# Controller.net
KiCad netlist of a schematic drawn in Altium Designer
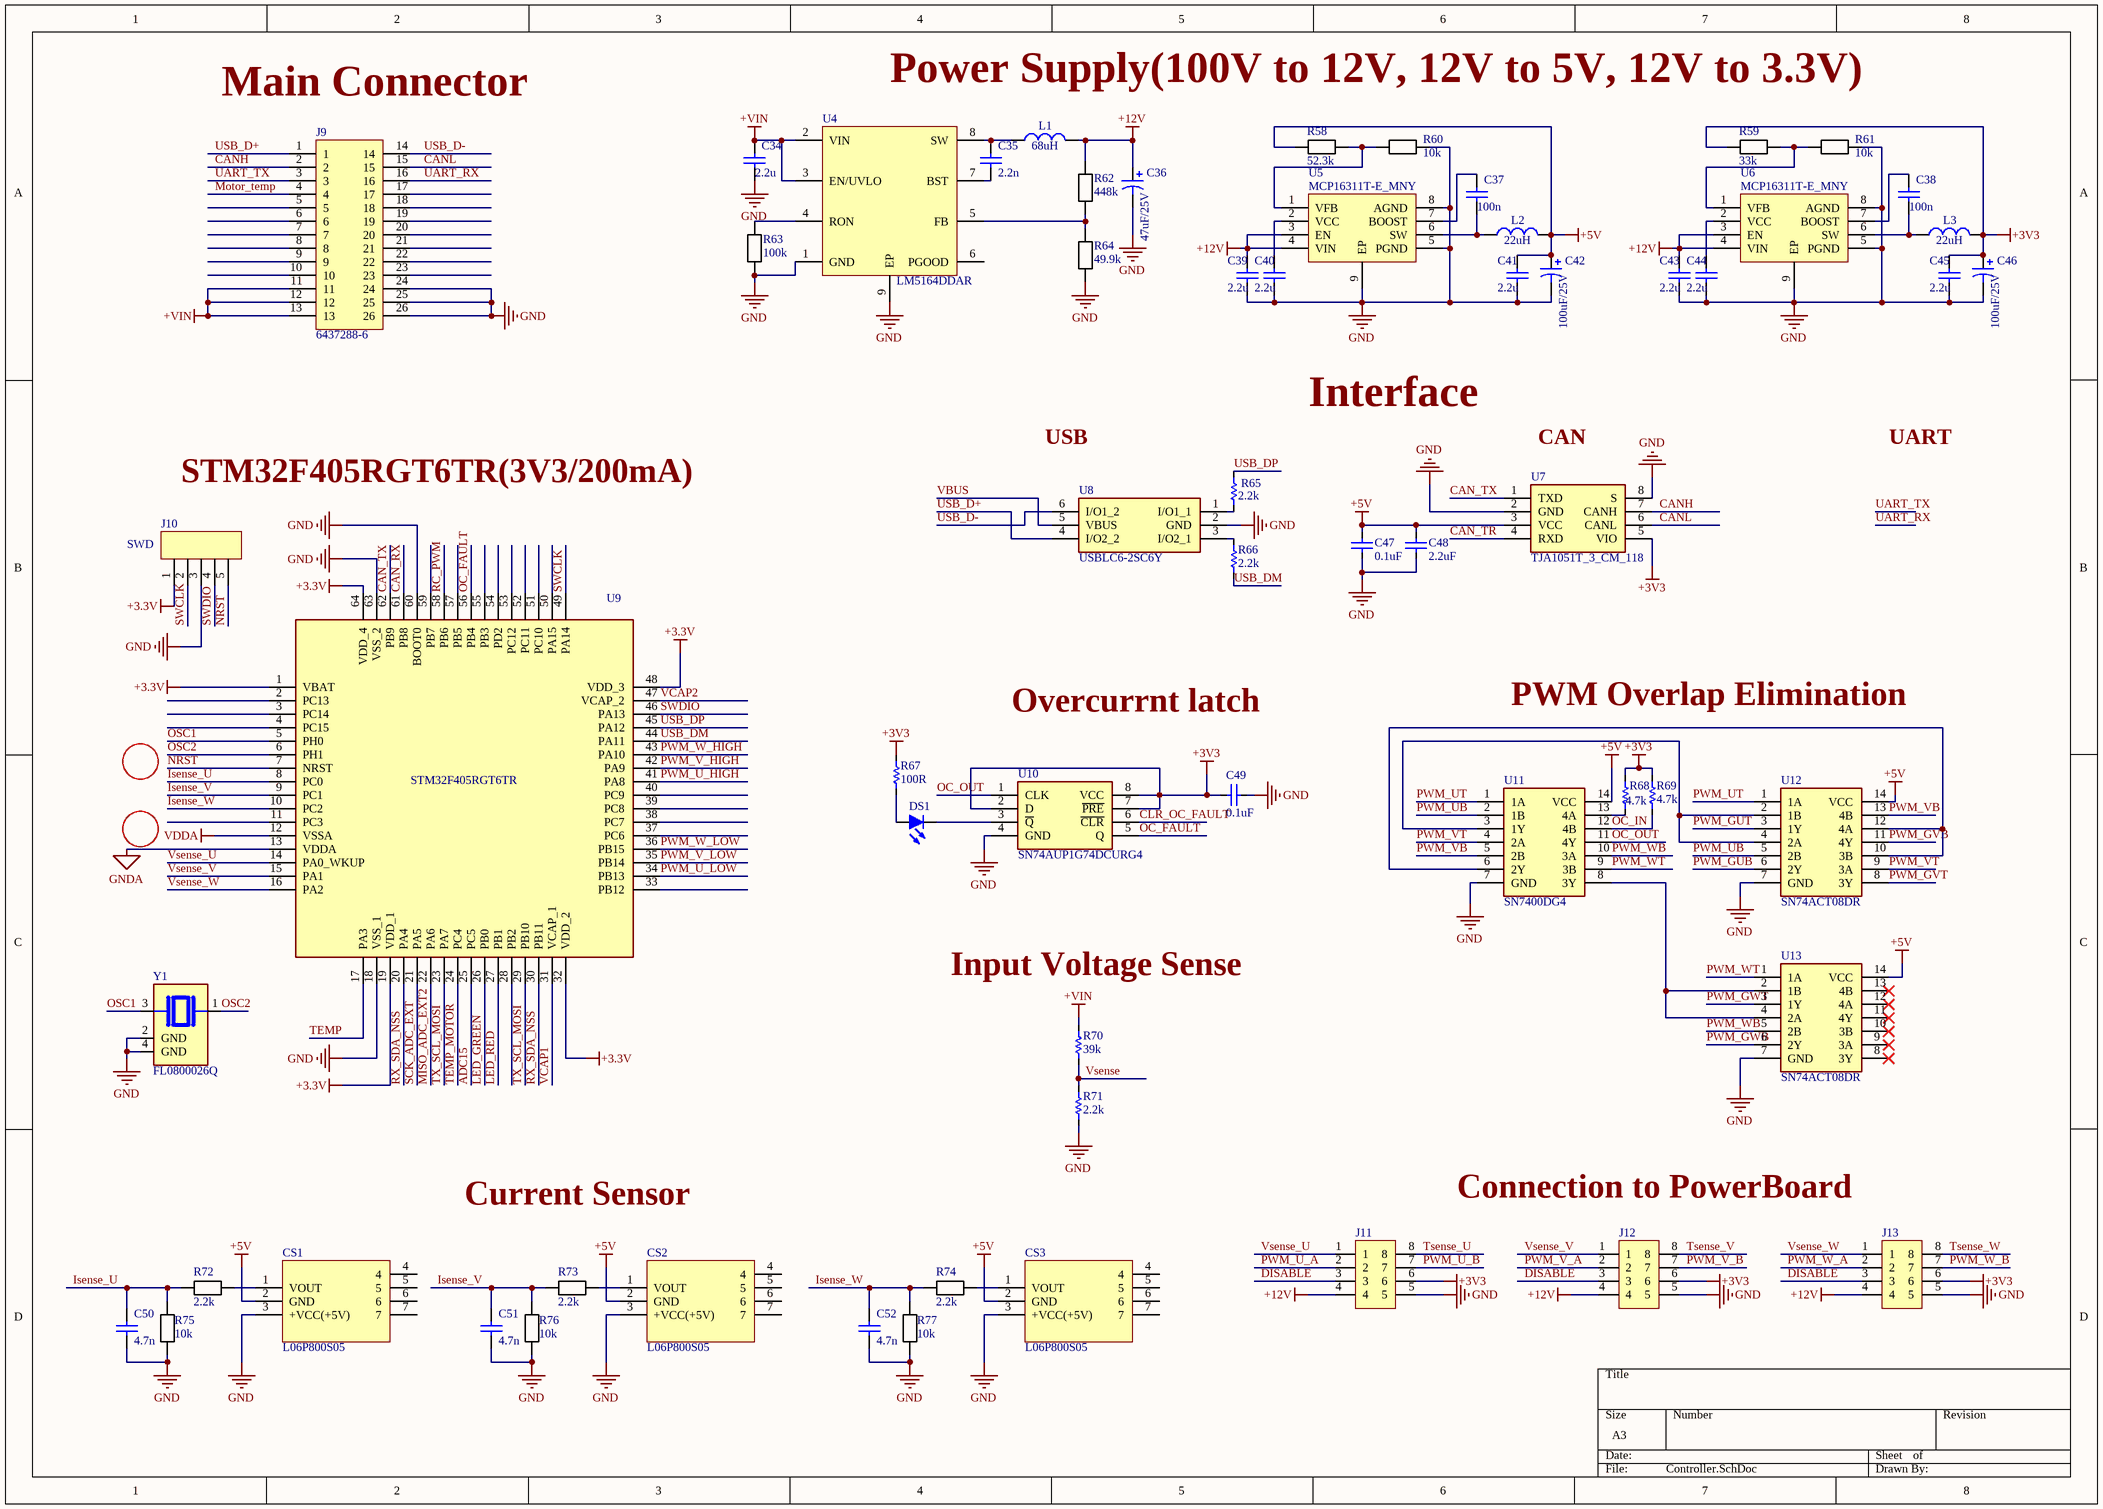
[diagram p0: Controller.SchDoc]

(export (version "E")
  (design (tool "Eeschema 10.0.6"))
  (components
    (comp (ref "C34")
      (value "2.2u")
      (footprint "*")
      (description "2.2uF ± 10% 100V")
      (libsource (lib "VESC_MotorController") (part "2.2uF ± 10% 100V"))
    )
    (comp (ref "C35")
      (value "2.2n")
      (footprint "C0603")
      (description "2.2nF ± 10% 50V")
      (fields (field (name "MANUFACTURER") "Yageo"))
      (libsource (lib "VESC_MotorController") (part "2.2nF ± 10% 50V"))
    )
    (comp (ref "C36")
      (value "47uF/25V")
      (footprint "*")
      (description "47uF ±20% 25V")
      (libsource (lib "Miscellaneous Devices") (part "Cap Pol1"))
    )
    (comp (ref "C37")
      (value "100n")
      (footprint "C0603")
      (description "100nF ± 10% 50V")
      (fields
        (field (name "MANUFACTURER") "Yageo")
        (field (name "MANUFACTURER PART NUMBER") "CC0603KRX7R9BB104")
      )
      (libsource (lib "VESC_MotorController") (part "100nF ± 10% 50V"))
    )
    (comp (ref "C38")
      (value "100n")
      (footprint "C0603")
      (description "100nF ± 10% 50V")
      (fields
        (field (name "MANUFACTURER") "Yageo")
        (field (name "MANUFACTURER PART NUMBER") "CC0603KRX7R9BB104")
      )
      (libsource (lib "VESC_MotorController") (part "100nF ± 10% 50V"))
    )
    (comp (ref "C39")
      (value "2.2u")
      (footprint "*")
      (description "2.2uF ± 10% 25V")
      (libsource (lib "VESC_MotorController") (part "2.2uF ± 10% 25V"))
    )
    (comp (ref "C40")
      (value "2.2u")
      (footprint "*")
      (description "2.2uF ± 10% 25V")
      (libsource (lib "VESC_MotorController") (part "2.2uF ± 10% 25V"))
    )
    (comp (ref "C41")
      (value "2.2u")
      (footprint "*")
      (description "2.2uF ± 10% 25V")
      (libsource (lib "VESC_MotorController") (part "2.2uF ± 10% 25V"))
    )
    (comp (ref "C42")
      (value "100uF/25V")
      (footprint "*")
      (description "100uF ±20% 25V")
      (libsource (lib "Miscellaneous Devices") (part "Cap Pol1"))
    )
    (comp (ref "C43")
      (value "2.2u")
      (footprint "*")
      (description "2.2uF ± 10% 25V")
      (libsource (lib "VESC_MotorController") (part "2.2uF ± 10% 25V"))
    )
    (comp (ref "C44")
      (value "2.2u")
      (footprint "*")
      (description "2.2uF ± 10% 25V")
      (libsource (lib "VESC_MotorController") (part "2.2uF ± 10% 25V"))
    )
    (comp (ref "C45")
      (value "2.2u")
      (footprint "*")
      (description "2.2uF ± 10% 25V")
      (libsource (lib "VESC_MotorController") (part "2.2uF ± 10% 25V"))
    )
    (comp (ref "C46")
      (value "100uF/25V")
      (footprint "*")
      (description "100uF ±20% 25V")
      (libsource (lib "Miscellaneous Devices") (part "Cap Pol1"))
    )
    (comp (ref "C47")
      (value "0.1uF")
      (footprint "SMD_C(0402)")
      (description "Multilayer Ceramic Capacitors MLCC - SMD/SMT 50 V 0.1uF X7R 0603 10%")
      (fields
        (field (name "MANUFACTURER") "Yageo")
        (field (name "MANUFACTURER PART NUMBER") "CC0603KPX7R9BB104")
      )
      (libsource (lib "CameraBoard") (part "Cap_1"))
    )
    (comp (ref "C48")
      (value "2.2uF")
      (footprint "SMD_C(0603)")
      (description "Multilayer Ceramic Capacitors MLCC - SMD/SMT 2.2 uF 50 VDC 10% 1206 X7R AEC-Q200")
      (fields
        (field (name "MANUFACTURER") "Yageo")
        (field (name "MANUFACTURER PART NUMBER") "GCM31CR71H225KA55K")
      )
      (libsource (lib "CameraBoard") (part "Cap_4"))
    )
    (comp (ref "C49")
      (value "0.1uF")
      (footprint "SMD_C(0402)")
      (description "Multilayer Ceramic Capacitors MLCC - SMD/SMT 50 V 0.1uF X7R 0603 10%")
      (fields
        (field (name "MANUFACTURER") "Yageo")
        (field (name "MANUFACTURER PART NUMBER") "CC0603KPX7R9BB104")
      )
      (libsource (lib "CameraBoard") (part "Cap_1"))
    )
    (comp (ref "C50")
      (value "4.7n")
      (footprint "C0603")
      (description "4.7nF ± 10% 50V")
      (fields (field (name "MANUFACTURER") "Yageo"))
      (libsource (lib "VESC_MotorController") (part "4.7nF ± 10% 50V"))
    )
    (comp (ref "C51")
      (value "4.7n")
      (footprint "C0603")
      (description "4.7nF ± 10% 50V")
      (fields (field (name "MANUFACTURER") "Yageo"))
      (libsource (lib "VESC_MotorController") (part "4.7nF ± 10% 50V"))
    )
    (comp (ref "C52")
      (value "4.7n")
      (footprint "C0603")
      (description "4.7nF ± 10% 50V")
      (fields (field (name "MANUFACTURER") "Yageo"))
      (libsource (lib "VESC_MotorController") (part "4.7nF ± 10% 50V"))
    )
    (comp (ref "CS1")
      (value "L06P800S05")
      (footprint "L06P800S05")
      (fields (field (name "MANUFACTURER") "Tamura"))
      (libsource (lib "L06P800S05") (part "L06P800S05"))
    )
    (comp (ref "CS2")
      (value "L06P800S05")
      (footprint "L06P800S05")
      (fields (field (name "MANUFACTURER") "Tamura"))
      (libsource (lib "L06P800S05") (part "L06P800S05"))
    )
    (comp (ref "CS3")
      (value "L06P800S05")
      (footprint "L06P800S05")
      (fields (field (name "MANUFACTURER") "Tamura"))
      (libsource (lib "L06P800S05") (part "L06P800S05"))
    )
    (comp (ref "DS1")
      (value "SML-D12U1WT86")
      (footprint "LED0603")
      (description "Typical RED GaAs LED")
      (fields (field (name "MANUFACTURER") "Rohm Semiconductor"))
      (libsource (lib "Humidity Regulator") (part "SML-D12U1WT86"))
    )
    (comp (ref "J9")
      (value "6437288-6")
      (footprint "64372886")
      (description "Header vert 26 way 4 row Tab Superseal")
      (fields (field (name "MANUFACTURER") "TE Connectivity"))
      (libsource (lib "VESC_MotorController") (part "6437288-6"))
    )
    (comp (ref "J10")
      (value "SWD")
      (footprint "Header-2.54m-5pin")
      (description "5PinConnector")
      (libsource (lib "VESC_MotorController_3") (part "5PinConnector"))
    )
    (comp (ref "J11")
      (value "~")
      (footprint "*")
      (description "2 Row 2.54mm Pitch 8 pins")
      (libsource (lib "VESC_MotorController") (part "PCB Header"))
    )
    (comp (ref "J12")
      (value "~")
      (footprint "*")
      (description "2 Row 2.54mm Pitch 8 pins")
      (libsource (lib "VESC_MotorController") (part "PCB Header"))
    )
    (comp (ref "J13")
      (value "~")
      (footprint "*")
      (description "2 Row 2.54mm Pitch 8 pins")
      (libsource (lib "VESC_MotorController") (part "PCB Header"))
    )
    (comp (ref "L1") (value "68uH") (footprint "*") (libsource (lib "WirelessCharger") (part "Inductor")))
    (comp (ref "L2") (value "22uH") (footprint "*") (libsource (lib "WirelessCharger") (part "Inductor")))
    (comp (ref "L3") (value "22uH") (footprint "*") (libsource (lib "WirelessCharger") (part "Inductor")))
    (comp (ref "R58")
      (value "52.3k")
      (footprint "R0603")
      (description "52.3 kohm 0.1W ±1%")
      (fields
        (field (name "MANUFACTURER PART NUMBER") "RC0603FR-0752K3L")
        (field (name "MANUFACTURER") "Yageo")
      )
      (libsource (lib "VESC_MotorController") (part "52.3 kohm 0.1W ±1%"))
    )
    (comp (ref "R59")
      (value "33k")
      (footprint "R0603")
      (description "33 kohm 0.1W ±1%")
      (fields
        (field (name "MANUFACTURER PART NUMBER") "RC0603FR-0733KL")
        (field (name "MANUFACTURER") "Yageo")
      )
      (libsource (lib "VESC_MotorController") (part "33 kohm 0.1W ±1%"))
    )
    (comp (ref "R60")
      (value "10k")
      (footprint "R0603")
      (description "10 kohm 0.1W ±1%")
      (fields
        (field (name "MANUFACTURER PART NUMBER") "RC0603FR-0710KL")
        (field (name "MANUFACTURER") "Yageo")
      )
      (libsource (lib "EMDO401_Charger_1") (part "10 kohm 0.1W ±1%"))
    )
    (comp (ref "R61")
      (value "10k")
      (footprint "R0603")
      (description "10 kohm 0.1W ±1%")
      (fields
        (field (name "MANUFACTURER PART NUMBER") "RC0603FR-0710KL")
        (field (name "MANUFACTURER") "Yageo")
      )
      (libsource (lib "EMDO401_Charger_1") (part "10 kohm 0.1W ±1%"))
    )
    (comp (ref "R62")
      (value "448k")
      (footprint "R0603")
      (description "448 kohm 0.1W ±1%")
      (fields
        (field (name "MANUFACTURER PART NUMBER") "RC0603FR-07448KL")
        (field (name "MANUFACTURER") "Yageo")
      )
      (libsource (lib "VESC_MotorController") (part "448 kohm 0.1W ±1%"))
    )
    (comp (ref "R63")
      (value "100k")
      (footprint "R0603")
      (description "100 kohm 0.1W ±1%")
      (fields
        (field (name "MANUFACTURER PART NUMBER") "RC0603FR-07100KL")
        (field (name "MANUFACTURER") "Yageo")
      )
      (libsource (lib "VESC_MotorController") (part "100 kohm 0.1W ±1%"))
    )
    (comp (ref "R64")
      (value "49.9k")
      (footprint "R0603")
      (description "49.9 kohm 0.1W ±1%")
      (fields
        (field (name "MANUFACTURER PART NUMBER") "RC0603FR-0749K9L")
        (field (name "MANUFACTURER") "Yageo")
      )
      (libsource (lib "VESC_MotorController") (part "49.9 kohm 0.1W ±1%"))
    )
    (comp (ref "R65")
      (value "2.2k")
      (footprint "SMD_R(0402)")
      (description "CRCW04024R02FKED")
      (fields (field (name "PUBLISHER") "Altium Limited"))
      (libsource (lib "CameraBoard") (part "Res Semi_2"))
    )
    (comp (ref "R66")
      (value "2.2k")
      (footprint "SMD_R(0402)")
      (description "CRCW04024R02FKED")
      (fields (field (name "PUBLISHER") "Altium Limited"))
      (libsource (lib "CameraBoard") (part "Res Semi_2"))
    )
    (comp (ref "R67")
      (value "100R")
      (footprint "SMD_R(0402)")
      (description "CRCW04024R02FKED")
      (fields (field (name "PUBLISHER") "Altium Limited"))
      (libsource (lib "CameraBoard") (part "Res Semi_1"))
    )
    (comp (ref "R68")
      (value "4.7k")
      (footprint "SMD_R(0402)")
      (description "CRCW04024R02FKED")
      (fields (field (name "PUBLISHER") "Altium Limited"))
      (libsource (lib "CameraBoard") (part "Res Semi_3"))
    )
    (comp (ref "R69")
      (value "4.7k")
      (footprint "SMD_R(0402)")
      (description "CRCW04024R02FKED")
      (fields (field (name "PUBLISHER") "Altium Limited"))
      (libsource (lib "CameraBoard") (part "Res Semi_3"))
    )
    (comp (ref "R70")
      (value "39k")
      (footprint "SMD_R(0402)")
      (description "CRCW04024R02FKED")
      (fields (field (name "PUBLISHER") "Altium Limited"))
      (libsource (lib "CameraBoard") (part "Res Semi_5"))
    )
    (comp (ref "R71")
      (value "2.2k")
      (footprint "SMD_R(0402)")
      (description "CRCW04024R02FKED")
      (fields (field (name "PUBLISHER") "Altium Limited"))
      (libsource (lib "CameraBoard") (part "Res Semi_5"))
    )
    (comp (ref "R72")
      (value "2.2k")
      (footprint "R0603")
      (description "2.2 kohm 0.1W ±1%")
      (fields
        (field (name "MANUFACTURER PART NUMBER") "RC0603FR-072K2L")
        (field (name "MANUFACTURER") "Yageo")
      )
      (libsource (lib "VESC_MotorController") (part "2.2 kohm 0.1W ±1%"))
    )
    (comp (ref "R73")
      (value "2.2k")
      (footprint "R0603")
      (description "2.2 kohm 0.1W ±1%")
      (fields
        (field (name "MANUFACTURER PART NUMBER") "RC0603FR-072K2L")
        (field (name "MANUFACTURER") "Yageo")
      )
      (libsource (lib "VESC_MotorController") (part "2.2 kohm 0.1W ±1%"))
    )
    (comp (ref "R74")
      (value "2.2k")
      (footprint "R0603")
      (description "2.2 kohm 0.1W ±1%")
      (fields
        (field (name "MANUFACTURER PART NUMBER") "RC0603FR-072K2L")
        (field (name "MANUFACTURER") "Yageo")
      )
      (libsource (lib "VESC_MotorController") (part "2.2 kohm 0.1W ±1%"))
    )
    (comp (ref "R75")
      (value "10k")
      (footprint "R0603")
      (description "10 kohm 0.1W ±1%")
      (fields
        (field (name "MANUFACTURER PART NUMBER") "RC0603FR-0710KL")
        (field (name "MANUFACTURER") "Yageo")
      )
      (libsource (lib "EMDO401_Charger_1") (part "10 kohm 0.1W ±1%"))
    )
    (comp (ref "R76")
      (value "10k")
      (footprint "R0603")
      (description "10 kohm 0.1W ±1%")
      (fields
        (field (name "MANUFACTURER PART NUMBER") "RC0603FR-0710KL")
        (field (name "MANUFACTURER") "Yageo")
      )
      (libsource (lib "EMDO401_Charger_1") (part "10 kohm 0.1W ±1%"))
    )
    (comp (ref "R77")
      (value "10k")
      (footprint "R0603")
      (description "10 kohm 0.1W ±1%")
      (fields
        (field (name "MANUFACTURER PART NUMBER") "RC0603FR-0710KL")
        (field (name "MANUFACTURER") "Yageo")
      )
      (libsource (lib "EMDO401_Charger_1") (part "10 kohm 0.1W ±1%"))
    )
    (comp (ref "U4")
      (value "LM5164DDAR")
      (footprint "SOIC-8(EPAD)")
      (fields (field (name "MANUFACTURER") "Texas Instruments"))
      (libsource (lib "VESC_MotorController") (part "LM5164DDAR"))
    )
    (comp (ref "U5")
      (value "MCP16311T-E_MNY")
      (footprint "MSOP-8")
      (description "Microchip, MCP16311T-E/MNY Step Down DC-DC Converter 1A Adjustable, 2  24 V 8-Pin, TDFN")
      (fields
        (field (name "MANUFACTURER") "Microchip")
        (field (name "MANUFACTURER PART NUMBER") "MCP16311T-E/MNY")
      )
      (libsource (lib "VESC_MotorController") (part "MCP16311T-E_MNY"))
    )
    (comp (ref "U6")
      (value "MCP16311T-E_MNY")
      (footprint "MSOP-8")
      (description "Microchip, MCP16311T-E/MNY Step Down DC-DC Converter 1A Adjustable, 2  24 V 8-Pin, TDFN")
      (fields
        (field (name "MANUFACTURER") "Microchip")
        (field (name "MANUFACTURER PART NUMBER") "MCP16311T-E/MNY")
      )
      (libsource (lib "VESC_MotorController") (part "MCP16311T-E_MNY"))
    )
    (comp (ref "U7")
      (value "TJA1051T_3_CM_118")
      (footprint "SOIC127P600X175-8N")
      (description "CAN Interface IC BL Advanced Automotive Analog")
      (fields
        (field (name "MOUSER PART NUMBER") "771-TJA1051T/3CM118")
        (field (name "MANUFACTURER_PART_NUMBER") "TJA1051T/3/CM,118")
      )
      (libsource (lib "TJA1051T_3_CM_118") (part "TJA1051T_3_CM_118"))
    )
    (comp (ref "U8")
      (value "USBLC6-2SC6Y")
      (footprint "SOT95P280X145-6N")
      (fields (field (name "MOUSER PART NUMBER") "511-USBLC6-2SC6Y"))
      (libsource (lib "USBLC6-2SC6Y") (part "USBLC6-2SC6Y"))
    )
    (comp (ref "U9")
      (value "STM32F405RGT6TR")
      (footprint "QFP50P1200X1200X160-64N")
      (fields (field (name "MOUSER PART NUMBER") "511-STM32F405RGT6TR"))
      (libsource (lib "STM32F405RGT6TR") (part "STM32F405RGT6TR"))
    )
    (comp (ref "U10")
      (value "SN74AUP1G74DCURG4")
      (footprint "SOP50P310X90-8N")
      (description "Flip Flops Lo PWR SNGL Pos Edge Trgrd DType FlipFlop")
      (fields (field (name "MOUSER PART NUMBER") "595-74AUP1G74DCURG4"))
      (libsource (lib "SN74AUP1G74DCURG4") (part "SN74AUP1G74DCURG4"))
    )
    (comp (ref "U11")
      (value "SN7400DG4")
      (footprint "SOIC127P600X175-14N")
      (description "NAND Gate 4-Element 2-IN Bipolar 14-Pin SOIC Tube")
      (fields (field (name "MOUSER PART NUMBER") "595-SN7400DG4"))
      (libsource (lib "SN7400DG4") (part "SN7400DG4"))
    )
    (comp (ref "U12")
      (value "SN74ACT08DR")
      (footprint "SOIC127P600X175-14N")
      (description "Texas Instruments SN74ACT08DR, AND Quad 2 Input AND, 4.5  5.5 V, 14-Pin SOIC")
      (fields (field (name "MOUSER PART NUMBER") "595-SN74ACT08DR"))
      (libsource (lib "SN74ACT08DR") (part "SN74ACT08DR"))
    )
    (comp (ref "U13")
      (value "SN74ACT08DR")
      (footprint "SOIC127P600X175-14N")
      (description "Texas Instruments SN74ACT08DR, AND Quad 2 Input AND, 4.5  5.5 V, 14-Pin SOIC")
      (fields (field (name "MOUSER PART NUMBER") "595-SN74ACT08DR"))
      (libsource (lib "SN74ACT08DR") (part "SN74ACT08DR"))
    )
    (comp (ref "Y1")
      (value "FL0800026Q")
      (footprint "XTAL_FL0800026Q")
      (description "8 MHz Â±30ppm Crystal 8pF 400 Ohms 4-SMD, No Lead")
      (fields (field (name "MF") "Diodes Incorporated"))
      (libsource (lib "FL0800026Q") (part "FL0800026Q"))
    )
  )
  (nets
    (net (code "1") (name "+3.3V") (class "Default")
      (node (ref "J10") (pin "1") (pinfunction "1_1") (pintype "passive"))
      (node (ref "U9") (pin "1") (pinfunction "VBAT_1") (pintype "passive"))
      (node (ref "U9") (pin "19") (pinfunction "VDD_1_19") (pintype "passive"))
      (node (ref "U9") (pin "32") (pinfunction "VDD_2_32") (pintype "passive"))
      (node (ref "U9") (pin "48") (pinfunction "VDD_3_48") (pintype "passive"))
      (node (ref "U9") (pin "64") (pinfunction "VDD_4_64") (pintype "passive"))
    )
    (net (code "2") (name "+3V3") (class "Default")
      (node (ref "C45") (pin "2") (pinfunction "2_2") (pintype "passive"))
      (node (ref "C46") (pin "1") (pinfunction "1_1") (pintype "passive"))
      (node (ref "C49") (pin "2") (pinfunction "2_2") (pintype "passive"))
      (node (ref "J11") (pin "6") (pinfunction "6_6") (pintype "passive"))
      (node (ref "J12") (pin "6") (pinfunction "6_6") (pintype "passive"))
      (node (ref "J13") (pin "6") (pinfunction "6_6") (pintype "passive"))
      (node (ref "L3") (pin "2") (pinfunction "2_2") (pintype "passive"))
      (node (ref "R59") (pin "1") (pinfunction "1_1") (pintype "passive"))
      (node (ref "R67") (pin "2") (pinfunction "2_2") (pintype "passive"))
      (node (ref "R68") (pin "2") (pinfunction "2_2") (pintype "passive"))
      (node (ref "R69") (pin "2") (pinfunction "2_2") (pintype "passive"))
      (node (ref "U10") (pin "2") (pinfunction "D_2") (pintype "passive"))
      (node (ref "U10") (pin "7") (pinfunction "~{PRE}_7") (pintype "passive"))
      (node (ref "U10") (pin "8") (pinfunction "VCC_8") (pintype "passive"))
      (node (ref "U7") (pin "5") (pinfunction "VIO_5") (pintype "passive"))
    )
    (net (code "3") (name "+5V") (class "Default")
      (node (ref "C41") (pin "2") (pinfunction "2_2") (pintype "passive"))
      (node (ref "C42") (pin "1") (pinfunction "1_1") (pintype "passive"))
      (node (ref "C47") (pin "2") (pinfunction "2_2") (pintype "passive"))
      (node (ref "C48") (pin "2") (pinfunction "2_2") (pintype "passive"))
      (node (ref "CS1") (pin "2") (pinfunction "GND_2") (pintype "passive"))
      (node (ref "CS2") (pin "2") (pinfunction "GND_2") (pintype "passive"))
      (node (ref "CS3") (pin "2") (pinfunction "GND_2") (pintype "passive"))
      (node (ref "L2") (pin "2") (pinfunction "2_2") (pintype "passive"))
      (node (ref "R58") (pin "1") (pinfunction "1_1") (pintype "passive"))
      (node (ref "U11") (pin "14") (pinfunction "VCC_14") (pintype "passive"))
      (node (ref "U12") (pin "14") (pinfunction "VCC_14") (pintype "passive"))
      (node (ref "U13") (pin "14") (pinfunction "VCC_14") (pintype "passive"))
      (node (ref "U7") (pin "3") (pinfunction "VCC_3") (pintype "power_in"))
    )
    (net (code "4") (name "+12V") (class "Default")
      (node (ref "C36") (pin "1") (pinfunction "1_1") (pintype "passive"))
      (node (ref "C39") (pin "2") (pinfunction "2_2") (pintype "passive"))
      (node (ref "C43") (pin "2") (pinfunction "2_2") (pintype "passive"))
      (node (ref "J11") (pin "4") (pinfunction "4_4") (pintype "passive"))
      (node (ref "J12") (pin "4") (pinfunction "4_4") (pintype "passive"))
      (node (ref "J13") (pin "4") (pinfunction "4_4") (pintype "passive"))
      (node (ref "L1") (pin "2") (pinfunction "2_2") (pintype "passive"))
      (node (ref "R62") (pin "2") (pinfunction "2_2") (pintype "passive"))
      (node (ref "U5") (pin "3") (pinfunction "EN_3") (pintype "passive"))
      (node (ref "U5") (pin "4") (pinfunction "VIN_4") (pintype "passive"))
      (node (ref "U6") (pin "3") (pinfunction "EN_3") (pintype "passive"))
      (node (ref "U6") (pin "4") (pinfunction "VIN_4") (pintype "passive"))
    )
    (net (code "5") (name "+VIN") (class "Default")
      (node (ref "C34") (pin "2") (pinfunction "2_2") (pintype "passive"))
      (node (ref "J9") (pin "11") (pinfunction "11_11") (pintype "passive"))
      (node (ref "J9") (pin "12") (pinfunction "12_12") (pintype "passive"))
      (node (ref "J9") (pin "13") (pinfunction "13_13") (pintype "passive"))
      (node (ref "R70") (pin "2") (pinfunction "2_2") (pintype "passive"))
      (node (ref "U4") (pin "2") (pinfunction "VIN_2") (pintype "passive"))
      (node (ref "U4") (pin "3") (pinfunction "EN/UVLO_3") (pintype "passive"))
    )
    (net (code "6") (name "/ADC15") (class "Default")
      (node (ref "U9") (pin "25") (pinfunction "PC5_25") (pintype "passive"))
    )
    (net (code "7") (name "/CANH") (class "Default")
      (node (ref "J9") (pin "2") (pinfunction "2_2") (pintype "passive"))
      (node (ref "U7") (pin "7") (pinfunction "CANH_7") (pintype "passive"))
    )
    (net (code "8") (name "/CANL") (class "Default")
      (node (ref "J9") (pin "15") (pinfunction "15_15") (pintype "passive"))
      (node (ref "U7") (pin "6") (pinfunction "CANL_6") (pintype "passive"))
    )
    (net (code "9") (name "/CAN_RX") (class "Default")
      (node (ref "U9") (pin "61") (pinfunction "PB8_61") (pintype "passive"))
    )
    (net (code "10") (name "/CAN_TR") (class "Default")
      (node (ref "U7") (pin "4") (pinfunction "RXD_4") (pintype "passive"))
    )
    (net (code "11") (name "/CAN_TX") (class "Default")
      (node (ref "U7") (pin "1") (pinfunction "TXD_1") (pintype "passive"))
      (node (ref "U9") (pin "62") (pinfunction "PB9_62") (pintype "passive"))
    )
    (net (code "12") (name "/CLR_OC_FAULT") (class "Default")
      (node (ref "U10") (pin "6") (pinfunction "~{CLR}_6") (pintype "passive"))
    )
    (net (code "13") (name "/DISABLE") (class "Default")
      (node (ref "J11") (pin "3") (pinfunction "3_3") (pintype "passive"))
      (node (ref "J12") (pin "3") (pinfunction "3_3") (pintype "passive"))
      (node (ref "J13") (pin "3") (pinfunction "3_3") (pintype "passive"))
    )
    (net (code "14") (name "/Isense_U") (class "Default")
      (node (ref "C50") (pin "2") (pinfunction "2_2") (pintype "passive"))
      (node (ref "R72") (pin "1") (pinfunction "1_1") (pintype "passive"))
      (node (ref "R75") (pin "2") (pinfunction "2_2") (pintype "passive"))
      (node (ref "U9") (pin "8") (pinfunction "PC0_8") (pintype "passive"))
    )
    (net (code "15") (name "/Isense_V") (class "Default")
      (node (ref "C51") (pin "2") (pinfunction "2_2") (pintype "passive"))
      (node (ref "R73") (pin "1") (pinfunction "1_1") (pintype "passive"))
      (node (ref "R76") (pin "2") (pinfunction "2_2") (pintype "passive"))
      (node (ref "U9") (pin "9") (pinfunction "PC1_9") (pintype "passive"))
    )
    (net (code "16") (name "/Isense_W") (class "Default")
      (node (ref "C52") (pin "2") (pinfunction "2_2") (pintype "passive"))
      (node (ref "R74") (pin "1") (pinfunction "1_1") (pintype "passive"))
      (node (ref "R77") (pin "2") (pinfunction "2_2") (pintype "passive"))
      (node (ref "U9") (pin "10") (pinfunction "PC2_10") (pintype "passive"))
    )
    (net (code "17") (name "/LED_GREEN") (class "Default")
      (node (ref "U9") (pin "26") (pinfunction "PB0_26") (pintype "passive"))
    )
    (net (code "18") (name "/LED_RED") (class "Default")
      (node (ref "U9") (pin "27") (pinfunction "PB1_27") (pintype "passive"))
    )
    (net (code "19") (name "/MISO_ADC_EXT2") (class "Default")
      (node (ref "U9") (pin "22") (pinfunction "PA6_22") (pintype "passive"))
    )
    (net (code "20") (name "/Motor_temp") (class "Default")
      (node (ref "J9") (pin "4") (pinfunction "4_4") (pintype "passive"))
    )
    (net (code "21") (name "/NRST") (class "Default")
      (node (ref "J10") (pin "5") (pinfunction "5_5") (pintype "passive"))
      (node (ref "U9") (pin "7") (pinfunction "NRST_7") (pintype "passive"))
    )
    (net (code "22") (name "/OC_FAULT") (class "Default")
      (node (ref "U10") (pin "5") (pinfunction "Q_5") (pintype "passive"))
      (node (ref "U9") (pin "56") (pinfunction "PB4_56") (pintype "passive"))
    )
    (net (code "23") (name "/OC_IN") (class "Default")
      (node (ref "R69") (pin "1") (pinfunction "1_1") (pintype "passive"))
      (node (ref "U11") (pin "12") (pinfunction "4B_12") (pintype "passive"))
    )
    (net (code "24") (name "/OC_OUT") (class "Default")
      (node (ref "U10") (pin "1") (pinfunction "CLK_1") (pintype "passive"))
      (node (ref "U11") (pin "11") (pinfunction "4Y_11") (pintype "passive"))
    )
    (net (code "25") (name "/OSC1") (class "Default")
      (node (ref "U9") (pin "5") (pinfunction "PH0_5") (pintype "passive"))
      (node (ref "Y1") (pin "3") (pinfunction "2_3") (pintype "passive"))
    )
    (net (code "26") (name "/OSC2") (class "Default")
      (node (ref "U9") (pin "6") (pinfunction "PH1_6") (pintype "passive"))
      (node (ref "Y1") (pin "1") (pinfunction "1_1") (pintype "passive"))
    )
    (net (code "27") (name "/PWM_GUB") (class "Default")
      (node (ref "U12") (pin "6") (pinfunction "2Y_6") (pintype "passive"))
    )
    (net (code "28") (name "/PWM_GUT") (class "Default")
      (node (ref "U12") (pin "3") (pinfunction "1Y_3") (pintype "passive"))
    )
    (net (code "29") (name "/PWM_GVB") (class "Default")
      (node (ref "U12") (pin "11") (pinfunction "4Y_11") (pintype "passive"))
    )
    (net (code "30") (name "/PWM_GVT") (class "Default")
      (node (ref "U12") (pin "8") (pinfunction "3Y_8") (pintype "passive"))
    )
    (net (code "31") (name "/PWM_GWB") (class "Default")
      (node (ref "U13") (pin "6") (pinfunction "2Y_6") (pintype "passive"))
    )
    (net (code "32") (name "/PWM_GWT") (class "Default")
      (node (ref "U13") (pin "3") (pinfunction "1Y_3") (pintype "passive"))
    )
    (net (code "33") (name "/PWM_UB") (class "Default")
      (node (ref "U11") (pin "2") (pinfunction "1B_2") (pintype "passive"))
      (node (ref "U12") (pin "5") (pinfunction "2B_5") (pintype "passive"))
    )
    (net (code "34") (name "/PWM_UT") (class "Default")
      (node (ref "U11") (pin "1") (pinfunction "1A_1") (pintype "passive"))
      (node (ref "U12") (pin "1") (pinfunction "1A_1") (pintype "passive"))
    )
    (net (code "35") (name "/PWM_U_A") (class "Default")
      (node (ref "J11") (pin "2") (pinfunction "2_2") (pintype "passive"))
    )
    (net (code "36") (name "/PWM_U_B") (class "Default")
      (node (ref "J11") (pin "7") (pinfunction "7_7") (pintype "passive"))
    )
    (net (code "37") (name "/PWM_U_HIGH") (class "Default")
      (node (ref "U9") (pin "41") (pinfunction "PA8_41") (pintype "passive"))
    )
    (net (code "38") (name "/PWM_U_LOW") (class "Default")
      (node (ref "U9") (pin "34") (pinfunction "PB13_34") (pintype "passive"))
    )
    (net (code "39") (name "/PWM_VB") (class "Default")
      (node (ref "U11") (pin "5") (pinfunction "2B_5") (pintype "passive"))
      (node (ref "U12") (pin "13") (pinfunction "4B_13") (pintype "passive"))
    )
    (net (code "40") (name "/PWM_VT") (class "Default")
      (node (ref "U11") (pin "4") (pinfunction "2A_4") (pintype "passive"))
      (node (ref "U12") (pin "9") (pinfunction "3A_9") (pintype "passive"))
    )
    (net (code "41") (name "/PWM_V_A") (class "Default")
      (node (ref "J12") (pin "2") (pinfunction "2_2") (pintype "passive"))
    )
    (net (code "42") (name "/PWM_V_B") (class "Default")
      (node (ref "J12") (pin "7") (pinfunction "7_7") (pintype "passive"))
    )
    (net (code "43") (name "/PWM_V_HIGH") (class "Default")
      (node (ref "U9") (pin "42") (pinfunction "PA9_42") (pintype "passive"))
    )
    (net (code "44") (name "/PWM_V_LOW") (class "Default")
      (node (ref "U9") (pin "35") (pinfunction "PB14_35") (pintype "passive"))
    )
    (net (code "45") (name "/PWM_WB") (class "Default")
      (node (ref "U11") (pin "10") (pinfunction "3A_10") (pintype "passive"))
      (node (ref "U13") (pin "5") (pinfunction "2B_5") (pintype "passive"))
    )
    (net (code "46") (name "/PWM_WT") (class "Default")
      (node (ref "U11") (pin "9") (pinfunction "3B_9") (pintype "passive"))
      (node (ref "U13") (pin "1") (pinfunction "1A_1") (pintype "passive"))
    )
    (net (code "47") (name "/PWM_W_A") (class "Default")
      (node (ref "J13") (pin "2") (pinfunction "2_2") (pintype "passive"))
    )
    (net (code "48") (name "/PWM_W_B") (class "Default")
      (node (ref "J13") (pin "7") (pinfunction "7_7") (pintype "passive"))
    )
    (net (code "49") (name "/PWM_W_HIGH") (class "Default")
      (node (ref "U9") (pin "43") (pinfunction "PA10_43") (pintype "passive"))
    )
    (net (code "50") (name "/PWM_W_LOW") (class "Default")
      (node (ref "U9") (pin "36") (pinfunction "PB15_36") (pintype "passive"))
    )
    (net (code "51") (name "/RC_PWM") (class "Default")
      (node (ref "U9") (pin "58") (pinfunction "PB6_58") (pintype "passive"))
    )
    (net (code "52") (name "/RX_SDA_NSS") (class "Default")
      (node (ref "U9") (pin "20") (pinfunction "PA4_20") (pintype "passive"))
      (node (ref "U9") (pin "30") (pinfunction "PB11_30") (pintype "passive"))
    )
    (net (code "53") (name "/SCK_ADC_EXT") (class "Default")
      (node (ref "U9") (pin "21") (pinfunction "PA5_21") (pintype "passive"))
    )
    (net (code "54") (name "/SWCLK") (class "Default")
      (node (ref "J10") (pin "2") (pinfunction "2_2") (pintype "passive"))
      (node (ref "U9") (pin "49") (pinfunction "PA14_49") (pintype "passive"))
    )
    (net (code "55") (name "/SWDIO") (class "Default")
      (node (ref "J10") (pin "4") (pinfunction "4_4") (pintype "passive"))
      (node (ref "U9") (pin "46") (pinfunction "PA13_46") (pintype "passive"))
    )
    (net (code "56") (name "/TEMP") (class "Default")
      (node (ref "U9") (pin "17") (pinfunction "PA3_17") (pintype "passive"))
    )
    (net (code "57") (name "/TEMP_MOTOR") (class "Default")
      (node (ref "U9") (pin "24") (pinfunction "PC4_24") (pintype "passive"))
    )
    (net (code "58") (name "/TX_SCL_MOSI") (class "Default")
      (node (ref "U9") (pin "23") (pinfunction "PA7_23") (pintype "passive"))
      (node (ref "U9") (pin "29") (pinfunction "PB10_29") (pintype "passive"))
    )
    (net (code "59") (name "/Tsense_U") (class "Default")
      (node (ref "J11") (pin "8") (pinfunction "8_8") (pintype "passive"))
    )
    (net (code "60") (name "/Tsense_V") (class "Default")
      (node (ref "J12") (pin "8") (pinfunction "8_8") (pintype "passive"))
    )
    (net (code "61") (name "/Tsense_W") (class "Default")
      (node (ref "J13") (pin "8") (pinfunction "8_8") (pintype "passive"))
    )
    (net (code "62") (name "/UART_RX") (class "Default")
      (node (ref "J9") (pin "16") (pinfunction "16_16") (pintype "passive"))
    )
    (net (code "63") (name "/UART_TX") (class "Default")
      (node (ref "J9") (pin "3") (pinfunction "3_3") (pintype "passive"))
    )
    (net (code "64") (name "/USB_D+") (class "Default")
      (node (ref "J9") (pin "1") (pinfunction "1_1") (pintype "passive"))
      (node (ref "U8") (pin "4") (pinfunction "I/O2_2_4") (pintype "passive"))
    )
    (net (code "65") (name "/USB_D-") (class "Default")
      (node (ref "J9") (pin "14") (pinfunction "14_14") (pintype "passive"))
      (node (ref "U8") (pin "6") (pinfunction "I/O1_2_6") (pintype "passive"))
    )
    (net (code "66") (name "/USB_DM") (class "Default")
      (node (ref "R66") (pin "2") (pinfunction "2_2") (pintype "passive"))
      (node (ref "U9") (pin "44") (pinfunction "PA11_44") (pintype "passive"))
    )
    (net (code "67") (name "/USB_DP") (class "Default")
      (node (ref "R65") (pin "2") (pinfunction "2_2") (pintype "passive"))
      (node (ref "U9") (pin "45") (pinfunction "PA12_45") (pintype "passive"))
    )
    (net (code "68") (name "/VBUS") (class "Default")
      (node (ref "U8") (pin "5") (pinfunction "VBUS_5") (pintype "passive"))
    )
    (net (code "69") (name "/VCAP1") (class "Default")
      (node (ref "U9") (pin "31") (pinfunction "VCAP_1_31") (pintype "passive"))
    )
    (net (code "70") (name "/VCAP2") (class "Default")
      (node (ref "U9") (pin "47") (pinfunction "VCAP_2_47") (pintype "passive"))
    )
    (net (code "71") (name "/Vsense") (class "Default")
      (node (ref "R70") (pin "1") (pinfunction "1_1") (pintype "passive"))
      (node (ref "R71") (pin "2") (pinfunction "2_2") (pintype "passive"))
    )
    (net (code "72") (name "/Vsense_U") (class "Default")
      (node (ref "J11") (pin "1") (pinfunction "1_1") (pintype "passive"))
      (node (ref "U9") (pin "14") (pinfunction "PA0_WKUP_14") (pintype "passive"))
    )
    (net (code "73") (name "/Vsense_V") (class "Default")
      (node (ref "J12") (pin "1") (pinfunction "1_1") (pintype "passive"))
      (node (ref "U9") (pin "15") (pinfunction "PA1_15") (pintype "passive"))
    )
    (net (code "74") (name "/Vsense_W") (class "Default")
      (node (ref "J13") (pin "1") (pinfunction "1_1") (pintype "passive"))
      (node (ref "U9") (pin "16") (pinfunction "PA2_16") (pintype "passive"))
    )
    (net (code "75") (name "GND") (class "Default")
      (node (ref "C34") (pin "1") (pinfunction "1_1") (pintype "passive"))
      (node (ref "C36") (pin "2") (pinfunction "2_2") (pintype "passive"))
      (node (ref "C39") (pin "1") (pinfunction "1_1") (pintype "passive"))
      (node (ref "C40") (pin "1") (pinfunction "1_1") (pintype "passive"))
      (node (ref "C41") (pin "1") (pinfunction "1_1") (pintype "passive"))
      (node (ref "C42") (pin "2") (pinfunction "2_2") (pintype "passive"))
      (node (ref "C43") (pin "1") (pinfunction "1_1") (pintype "passive"))
      (node (ref "C44") (pin "1") (pinfunction "1_1") (pintype "passive"))
      (node (ref "C45") (pin "1") (pinfunction "1_1") (pintype "passive"))
      (node (ref "C46") (pin "2") (pinfunction "2_2") (pintype "passive"))
      (node (ref "C47") (pin "1") (pinfunction "1_1") (pintype "passive"))
      (node (ref "C48") (pin "1") (pinfunction "1_1") (pintype "passive"))
      (node (ref "C49") (pin "1") (pinfunction "1_1") (pintype "passive"))
      (node (ref "C50") (pin "1") (pinfunction "1_1") (pintype "passive"))
      (node (ref "C51") (pin "1") (pinfunction "1_1") (pintype "passive"))
      (node (ref "C52") (pin "1") (pinfunction "1_1") (pintype "passive"))
      (node (ref "CS1") (pin "3") (pinfunction "+VCC(+5V)_3") (pintype "passive"))
      (node (ref "CS2") (pin "3") (pinfunction "+VCC(+5V)_3") (pintype "passive"))
      (node (ref "CS3") (pin "3") (pinfunction "+VCC(+5V)_3") (pintype "passive"))
      (node (ref "J10") (pin "3") (pinfunction "3_3") (pintype "passive"))
      (node (ref "J11") (pin "5") (pinfunction "5_5") (pintype "passive"))
      (node (ref "J12") (pin "5") (pinfunction "5_5") (pintype "passive"))
      (node (ref "J13") (pin "5") (pinfunction "5_5") (pintype "passive"))
      (node (ref "J9") (pin "24") (pinfunction "24_24") (pintype "passive"))
      (node (ref "J9") (pin "25") (pinfunction "25_25") (pintype "passive"))
      (node (ref "J9") (pin "26") (pinfunction "26_26") (pintype "passive"))
      (node (ref "R60") (pin "1") (pinfunction "1_1") (pintype "passive"))
      (node (ref "R61") (pin "1") (pinfunction "1_1") (pintype "passive"))
      (node (ref "R63") (pin "1") (pinfunction "1_1") (pintype "passive"))
      (node (ref "R64") (pin "1") (pinfunction "1_1") (pintype "passive"))
      (node (ref "R71") (pin "1") (pinfunction "1_1") (pintype "passive"))
      (node (ref "R75") (pin "1") (pinfunction "1_1") (pintype "passive"))
      (node (ref "R76") (pin "1") (pinfunction "1_1") (pintype "passive"))
      (node (ref "R77") (pin "1") (pinfunction "1_1") (pintype "passive"))
      (node (ref "U10") (pin "4") (pinfunction "GND_4") (pintype "passive"))
      (node (ref "U11") (pin "7") (pinfunction "GND_7") (pintype "passive"))
      (node (ref "U12") (pin "7") (pinfunction "GND_7") (pintype "passive"))
      (node (ref "U13") (pin "7") (pinfunction "GND_7") (pintype "passive"))
      (node (ref "U4") (pin "1") (pinfunction "GND_1") (pintype "passive"))
      (node (ref "U4") (pin "9") (pinfunction "EP_9") (pintype "passive"))
      (node (ref "U5") (pin "5") (pinfunction "PGND_5") (pintype "passive"))
      (node (ref "U5") (pin "8") (pinfunction "AGND_8") (pintype "passive"))
      (node (ref "U5") (pin "9") (pinfunction "EP_9") (pintype "passive"))
      (node (ref "U6") (pin "5") (pinfunction "PGND_5") (pintype "passive"))
      (node (ref "U6") (pin "8") (pinfunction "AGND_8") (pintype "passive"))
      (node (ref "U6") (pin "9") (pinfunction "EP_9") (pintype "passive"))
      (node (ref "U7") (pin "2") (pinfunction "GND_2") (pintype "passive"))
      (node (ref "U7") (pin "8") (pinfunction "S_8") (pintype "passive"))
      (node (ref "U8") (pin "2") (pinfunction "GND_2") (pintype "passive"))
      (node (ref "U9") (pin "18") (pinfunction "VSS_1_18") (pintype "passive"))
      (node (ref "U9") (pin "60") (pinfunction "BOOT0_60") (pintype "passive"))
      (node (ref "U9") (pin "63") (pinfunction "VSS_2_63") (pintype "passive"))
      (node (ref "Y1") (pin "2") (pinfunction "GND_2") (pintype "power_in"))
      (node (ref "Y1") (pin "4") (pinfunction "GND_4") (pintype "power_in"))
    )
    (net (code "76") (name "GNDA") (class "Default")
      (node (ref "U9") (pin "13") (pinfunction "VDDA_13") (pintype "passive"))
    )
    (net (code "77") (name "Net-(CS1-VOUT)") (class "Default")
      (node (ref "CS1") (pin "1") (pinfunction "VOUT_1") (pintype "passive"))
      (node (ref "R72") (pin "2") (pinfunction "2_2") (pintype "passive"))
    )
    (net (code "78") (name "Net-(CS2-VOUT)") (class "Default")
      (node (ref "CS2") (pin "1") (pinfunction "VOUT_1") (pintype "passive"))
      (node (ref "R73") (pin "2") (pinfunction "2_2") (pintype "passive"))
    )
    (net (code "79") (name "Net-(CS3-VOUT)") (class "Default")
      (node (ref "CS3") (pin "1") (pinfunction "VOUT_1") (pintype "passive"))
      (node (ref "R74") (pin "2") (pinfunction "2_2") (pintype "passive"))
    )
    (net (code "80") (name "Net-(DS1-PadA)") (class "Default")
      (node (ref "DS1") (pin "A") (pinfunction "A_A") (pintype "passive"))
      (node (ref "R67") (pin "1") (pinfunction "1_1") (pintype "passive"))
    )
    (net (code "81") (name "Net-(U4-BST)") (class "Default")
      (node (ref "C35") (pin "1") (pinfunction "1_1") (pintype "passive"))
      (node (ref "U4") (pin "7") (pinfunction "BST_7") (pintype "passive"))
    )
    (net (code "82") (name "Net-(U4-FB)") (class "Default")
      (node (ref "R62") (pin "1") (pinfunction "1_1") (pintype "passive"))
      (node (ref "R64") (pin "2") (pinfunction "2_2") (pintype "passive"))
      (node (ref "U4") (pin "5") (pinfunction "FB_5") (pintype "passive"))
    )
    (net (code "83") (name "Net-(U4-RON)") (class "Default")
      (node (ref "R63") (pin "2") (pinfunction "2_2") (pintype "passive"))
      (node (ref "U4") (pin "4") (pinfunction "RON_4") (pintype "passive"))
    )
    (net (code "84") (name "Net-(U4-SW)") (class "Default")
      (node (ref "C35") (pin "2") (pinfunction "2_2") (pintype "passive"))
      (node (ref "L1") (pin "1") (pinfunction "1_1") (pintype "passive"))
      (node (ref "U4") (pin "8") (pinfunction "SW_8") (pintype "passive"))
    )
    (net (code "85") (name "Net-(U5-BOOST)") (class "Default")
      (node (ref "C37") (pin "2") (pinfunction "2_2") (pintype "passive"))
      (node (ref "U5") (pin "7") (pinfunction "BOOST_7") (pintype "passive"))
    )
    (net (code "86") (name "Net-(U5-SW)") (class "Default")
      (node (ref "C37") (pin "1") (pinfunction "1_1") (pintype "passive"))
      (node (ref "L2") (pin "1") (pinfunction "1_1") (pintype "passive"))
      (node (ref "U5") (pin "6") (pinfunction "SW_6") (pintype "passive"))
    )
    (net (code "87") (name "Net-(U5-VCC)") (class "Default")
      (node (ref "C40") (pin "2") (pinfunction "2_2") (pintype "passive"))
      (node (ref "U5") (pin "2") (pinfunction "VCC_2") (pintype "passive"))
    )
    (net (code "88") (name "Net-(U5-VFB)") (class "Default")
      (node (ref "R58") (pin "2") (pinfunction "2_2") (pintype "passive"))
      (node (ref "R60") (pin "2") (pinfunction "2_2") (pintype "passive"))
      (node (ref "U5") (pin "1") (pinfunction "VFB_1") (pintype "passive"))
    )
    (net (code "89") (name "Net-(U6-BOOST)") (class "Default")
      (node (ref "C38") (pin "2") (pinfunction "2_2") (pintype "passive"))
      (node (ref "U6") (pin "7") (pinfunction "BOOST_7") (pintype "passive"))
    )
    (net (code "90") (name "Net-(U6-SW)") (class "Default")
      (node (ref "C38") (pin "1") (pinfunction "1_1") (pintype "passive"))
      (node (ref "L3") (pin "1") (pinfunction "1_1") (pintype "passive"))
      (node (ref "U6") (pin "6") (pinfunction "SW_6") (pintype "passive"))
    )
    (net (code "91") (name "Net-(U6-VCC)") (class "Default")
      (node (ref "C44") (pin "2") (pinfunction "2_2") (pintype "passive"))
      (node (ref "U6") (pin "2") (pinfunction "VCC_2") (pintype "passive"))
    )
    (net (code "92") (name "Net-(U6-VFB)") (class "Default")
      (node (ref "R59") (pin "2") (pinfunction "2_2") (pintype "passive"))
      (node (ref "R61") (pin "2") (pinfunction "2_2") (pintype "passive"))
      (node (ref "U6") (pin "1") (pinfunction "VFB_1") (pintype "passive"))
    )
    (net (code "93") (name "Net-(U8-I{slash}O1_1)") (class "Default")
      (node (ref "R65") (pin "1") (pinfunction "1_1") (pintype "passive"))
      (node (ref "U8") (pin "1") (pinfunction "I/O1_1_1") (pintype "passive"))
    )
    (net (code "94") (name "Net-(U8-I{slash}O2_1)") (class "Default")
      (node (ref "R66") (pin "1") (pinfunction "1_1") (pintype "passive"))
      (node (ref "U8") (pin "3") (pinfunction "I/O2_1_3") (pintype "passive"))
    )
    (net (code "95") (name "Net-(U10-~{Q})") (class "Default")
      (node (ref "DS1") (pin "C") (pinfunction "C_C") (pintype "passive"))
      (node (ref "U10") (pin "3") (pinfunction "~{Q}_3") (pintype "passive"))
    )
    (net (code "96") (name "Net-(U11-1Y)") (class "Default")
      (node (ref "U11") (pin "3") (pinfunction "1Y_3") (pintype "passive"))
      (node (ref "U12") (pin "2") (pinfunction "1B_2") (pintype "passive"))
      (node (ref "U12") (pin "4") (pinfunction "2A_4") (pintype "passive"))
    )
    (net (code "97") (name "Net-(U11-2Y)") (class "Default")
      (node (ref "U11") (pin "6") (pinfunction "2Y_6") (pintype "passive"))
      (node (ref "U12") (pin "10") (pinfunction "3B_10") (pintype "passive"))
      (node (ref "U12") (pin "12") (pinfunction "4A_12") (pintype "passive"))
    )
    (net (code "98") (name "Net-(U11-3Y)") (class "Default")
      (node (ref "U11") (pin "8") (pinfunction "3Y_8") (pintype "passive"))
      (node (ref "U13") (pin "2") (pinfunction "1B_2") (pintype "passive"))
      (node (ref "U13") (pin "4") (pinfunction "2A_4") (pintype "passive"))
    )
    (net (code "99") (name "Net-(U11-4A)") (class "Default")
      (node (ref "R68") (pin "1") (pinfunction "1_1") (pintype "passive"))
      (node (ref "U11") (pin "13") (pinfunction "4A_13") (pintype "passive"))
    )
    (net (code "100") (name "VDDA") (class "Default")
      (node (ref "U9") (pin "12") (pinfunction "VSSA_12") (pintype "passive"))
    )
    (net (code "101") (name "unconnected-(CS1-Pad4)") (class "Default")
      (node (ref "CS1") (pin "4") (pinfunction "4_4") (pintype "passive"))
    )
    (net (code "102") (name "unconnected-(CS1-Pad5)") (class "Default")
      (node (ref "CS1") (pin "5") (pinfunction "5_5") (pintype "passive"))
    )
    (net (code "103") (name "unconnected-(CS1-Pad6)") (class "Default")
      (node (ref "CS1") (pin "6") (pinfunction "6_6") (pintype "passive"))
    )
    (net (code "104") (name "unconnected-(CS1-Pad7)") (class "Default")
      (node (ref "CS1") (pin "7") (pinfunction "7_7") (pintype "passive"))
    )
    (net (code "105") (name "unconnected-(CS2-Pad4)") (class "Default")
      (node (ref "CS2") (pin "4") (pinfunction "4_4") (pintype "passive"))
    )
    (net (code "106") (name "unconnected-(CS2-Pad5)") (class "Default")
      (node (ref "CS2") (pin "5") (pinfunction "5_5") (pintype "passive"))
    )
    (net (code "107") (name "unconnected-(CS2-Pad6)") (class "Default")
      (node (ref "CS2") (pin "6") (pinfunction "6_6") (pintype "passive"))
    )
    (net (code "108") (name "unconnected-(CS2-Pad7)") (class "Default")
      (node (ref "CS2") (pin "7") (pinfunction "7_7") (pintype "passive"))
    )
    (net (code "109") (name "unconnected-(CS3-Pad4)") (class "Default")
      (node (ref "CS3") (pin "4") (pinfunction "4_4") (pintype "passive"))
    )
    (net (code "110") (name "unconnected-(CS3-Pad5)") (class "Default")
      (node (ref "CS3") (pin "5") (pinfunction "5_5") (pintype "passive"))
    )
    (net (code "111") (name "unconnected-(CS3-Pad6)") (class "Default")
      (node (ref "CS3") (pin "6") (pinfunction "6_6") (pintype "passive"))
    )
    (net (code "112") (name "unconnected-(CS3-Pad7)") (class "Default")
      (node (ref "CS3") (pin "7") (pinfunction "7_7") (pintype "passive"))
    )
    (net (code "113") (name "unconnected-(J9-Pad5)") (class "Default")
      (node (ref "J9") (pin "5") (pinfunction "5_5") (pintype "passive"))
    )
    (net (code "114") (name "unconnected-(J9-Pad6)") (class "Default")
      (node (ref "J9") (pin "6") (pinfunction "6_6") (pintype "passive"))
    )
    (net (code "115") (name "unconnected-(J9-Pad7)") (class "Default")
      (node (ref "J9") (pin "7") (pinfunction "7_7") (pintype "passive"))
    )
    (net (code "116") (name "unconnected-(J9-Pad8)") (class "Default")
      (node (ref "J9") (pin "8") (pinfunction "8_8") (pintype "passive"))
    )
    (net (code "117") (name "unconnected-(J9-Pad9)") (class "Default")
      (node (ref "J9") (pin "9") (pinfunction "9_9") (pintype "passive"))
    )
    (net (code "118") (name "unconnected-(J9-Pad10)") (class "Default")
      (node (ref "J9") (pin "10") (pinfunction "10_10") (pintype "passive"))
    )
    (net (code "119") (name "unconnected-(J9-Pad17)") (class "Default")
      (node (ref "J9") (pin "17") (pinfunction "17_17") (pintype "passive"))
    )
    (net (code "120") (name "unconnected-(J9-Pad18)") (class "Default")
      (node (ref "J9") (pin "18") (pinfunction "18_18") (pintype "passive"))
    )
    (net (code "121") (name "unconnected-(J9-Pad19)") (class "Default")
      (node (ref "J9") (pin "19") (pinfunction "19_19") (pintype "passive"))
    )
    (net (code "122") (name "unconnected-(J9-Pad20)") (class "Default")
      (node (ref "J9") (pin "20") (pinfunction "20_20") (pintype "passive"))
    )
    (net (code "123") (name "unconnected-(J9-Pad21)") (class "Default")
      (node (ref "J9") (pin "21") (pinfunction "21_21") (pintype "passive"))
    )
    (net (code "124") (name "unconnected-(J9-Pad22)") (class "Default")
      (node (ref "J9") (pin "22") (pinfunction "22_22") (pintype "passive"))
    )
    (net (code "125") (name "unconnected-(J9-Pad23)") (class "Default")
      (node (ref "J9") (pin "23") (pinfunction "23_23") (pintype "passive"))
    )
    (net (code "126") (name "unconnected-(U4-PGOOD-Pad6)") (class "Default")
      (node (ref "U4") (pin "6") (pinfunction "PGOOD_6") (pintype "passive"))
    )
    (net (code "127") (name "unconnected-(U9-PA15-Pad50)") (class "Default")
      (node (ref "U9") (pin "50") (pinfunction "PA15_50") (pintype "passive"))
    )
    (net (code "128") (name "unconnected-(U9-PB2-Pad28)") (class "Default")
      (node (ref "U9") (pin "28") (pinfunction "PB2_28") (pintype "passive"))
    )
    (net (code "129") (name "unconnected-(U9-PB3-Pad55)") (class "Default")
      (node (ref "U9") (pin "55") (pinfunction "PB3_55") (pintype "passive"))
    )
    (net (code "130") (name "unconnected-(U9-PB5-Pad57)") (class "Default")
      (node (ref "U9") (pin "57") (pinfunction "PB5_57") (pintype "passive"))
    )
    (net (code "131") (name "unconnected-(U9-PB7-Pad59)") (class "Default")
      (node (ref "U9") (pin "59") (pinfunction "PB7_59") (pintype "passive"))
    )
    (net (code "132") (name "unconnected-(U9-PB12-Pad33)") (class "Default")
      (node (ref "U9") (pin "33") (pinfunction "PB12_33") (pintype "passive"))
    )
    (net (code "133") (name "unconnected-(U9-PC3-Pad11)") (class "Default")
      (node (ref "U9") (pin "11") (pinfunction "PC3_11") (pintype "passive"))
    )
    (net (code "134") (name "unconnected-(U9-PC6-Pad37)") (class "Default")
      (node (ref "U9") (pin "37") (pinfunction "PC6_37") (pintype "passive"))
    )
    (net (code "135") (name "unconnected-(U9-PC7-Pad38)") (class "Default")
      (node (ref "U9") (pin "38") (pinfunction "PC7_38") (pintype "passive"))
    )
    (net (code "136") (name "unconnected-(U9-PC8-Pad39)") (class "Default")
      (node (ref "U9") (pin "39") (pinfunction "PC8_39") (pintype "passive"))
    )
    (net (code "137") (name "unconnected-(U9-PC9-Pad40)") (class "Default")
      (node (ref "U9") (pin "40") (pinfunction "PC9_40") (pintype "passive"))
    )
    (net (code "138") (name "unconnected-(U9-PC10-Pad51)") (class "Default")
      (node (ref "U9") (pin "51") (pinfunction "PC10_51") (pintype "passive"))
    )
    (net (code "139") (name "unconnected-(U9-PC11-Pad52)") (class "Default")
      (node (ref "U9") (pin "52") (pinfunction "PC11_52") (pintype "passive"))
    )
    (net (code "140") (name "unconnected-(U9-PC12-Pad53)") (class "Default")
      (node (ref "U9") (pin "53") (pinfunction "PC12_53") (pintype "passive"))
    )
    (net (code "141") (name "unconnected-(U9-PC13-Pad2)") (class "Default")
      (node (ref "U9") (pin "2") (pinfunction "PC13_2") (pintype "passive"))
    )
    (net (code "142") (name "unconnected-(U9-PC14-Pad3)") (class "Default")
      (node (ref "U9") (pin "3") (pinfunction "PC14_3") (pintype "passive"))
    )
    (net (code "143") (name "unconnected-(U9-PC15-Pad4)") (class "Default")
      (node (ref "U9") (pin "4") (pinfunction "PC15_4") (pintype "passive"))
    )
    (net (code "144") (name "unconnected-(U9-PD2-Pad54)") (class "Default")
      (node (ref "U9") (pin "54") (pinfunction "PD2_54") (pintype "passive"))
    )
    (net (code "145") (name "unconnected-(U13-3A-Pad9)") (class "Default")
      (node (ref "U13") (pin "9") (pinfunction "3A_9") (pintype "passive+no_connect"))
    )
    (net (code "146") (name "unconnected-(U13-3B-Pad10)") (class "Default")
      (node (ref "U13") (pin "10") (pinfunction "3B_10") (pintype "passive+no_connect"))
    )
    (net (code "147") (name "unconnected-(U13-3Y-Pad8)") (class "Default")
      (node (ref "U13") (pin "8") (pinfunction "3Y_8") (pintype "passive+no_connect"))
    )
    (net (code "148") (name "unconnected-(U13-4A-Pad12)") (class "Default")
      (node (ref "U13") (pin "12") (pinfunction "4A_12") (pintype "passive+no_connect"))
    )
    (net (code "149") (name "unconnected-(U13-4B-Pad13)") (class "Default")
      (node (ref "U13") (pin "13") (pinfunction "4B_13") (pintype "passive+no_connect"))
    )
    (net (code "150") (name "unconnected-(U13-4Y-Pad11)") (class "Default")
      (node (ref "U13") (pin "11") (pinfunction "4Y_11") (pintype "passive+no_connect"))
    )
  )
)
